# usb-isolator.net
KiCad netlist of a schematic drawn in EAGLE
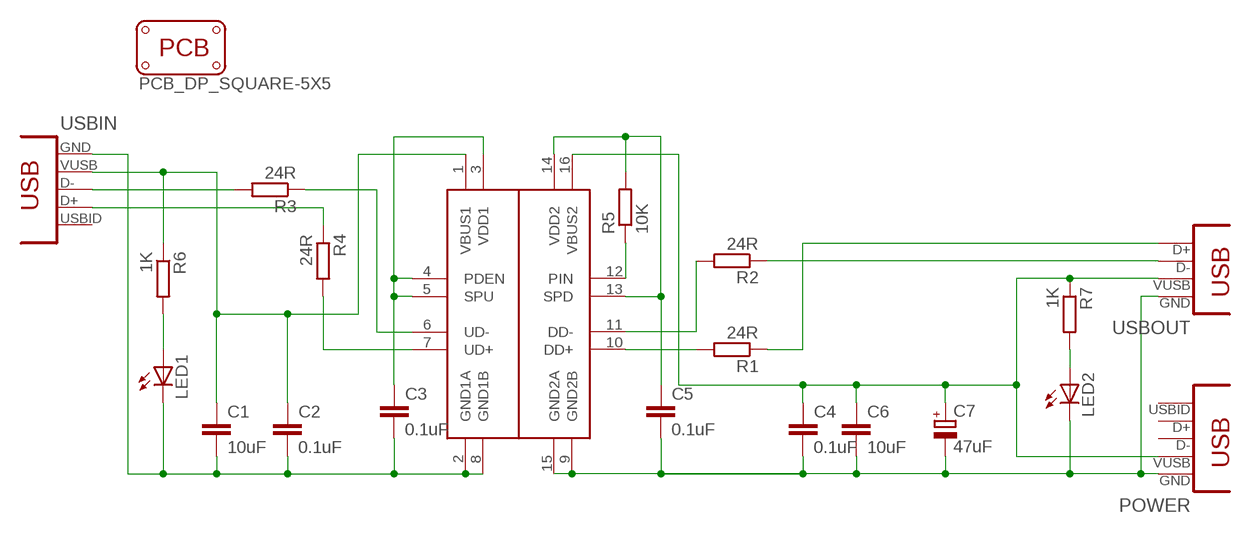
[diagram p0: schematic, sheet 1]

(export (version "E")
  (design (tool "Eeschema 10.0.6"))
  (components
    (comp (ref "C1")
      (value "10uF")
      (footprint "eagle-import:C0805K")
      (libsource (lib "eagle-import") (part "C-EUC0805K"))
    )
    (comp (ref "C2")
      (value "0.1uF")
      (footprint "eagle-import:C0805K")
      (libsource (lib "eagle-import") (part "C-EUC0805K"))
    )
    (comp (ref "C3")
      (value "0.1uF")
      (footprint "eagle-import:C0805K")
      (libsource (lib "eagle-import") (part "C-EUC0805K"))
    )
    (comp (ref "C4")
      (value "0.1uF")
      (footprint "eagle-import:C0805K")
      (libsource (lib "eagle-import") (part "C-EUC0805K"))
    )
    (comp (ref "C5")
      (value "0.1uF")
      (footprint "eagle-import:C0805K")
      (libsource (lib "eagle-import") (part "C-EUC0805K"))
    )
    (comp (ref "C6")
      (value "10uF")
      (footprint "eagle-import:C0805K")
      (libsource (lib "eagle-import") (part "C-EUC0805K"))
    )
    (comp (ref "C7")
      (value "47uF")
      (footprint "eagle-import:D_7343-31W")
      (libsource (lib "eagle-import") (part "CPOL-EUD/7343-31W"))
    )
    (comp (ref "IC1")
      (value "ADUM3160BRWZ")
      (footprint "eagle-import:SO16W")
      (libsource (lib "eagle-import") (part "ADUM3160BRWZ"))
    )
    (comp (ref "LED1")
      (value "LED-0805")
      (footprint "eagle-import:LED-805")
      (libsource (lib "eagle-import") (part "LED-0805"))
    )
    (comp (ref "LED2")
      (value "LED-0805")
      (footprint "eagle-import:LED-805")
      (libsource (lib "eagle-import") (part "LED-0805"))
    )
    (comp (ref "POWER")
      (value "CON-USB-F-MINI-B")
      (footprint "eagle-import:CONN_USB_MINI-B")
      (libsource (lib "eagle-import") (part "CON-USB-F-MINI-B"))
    )
    (comp (ref "R1")
      (value "24R")
      (footprint "eagle-import:M0805")
      (libsource (lib "eagle-import") (part "R-EU_M0805"))
    )
    (comp (ref "R2")
      (value "24R")
      (footprint "eagle-import:M0805")
      (libsource (lib "eagle-import") (part "R-EU_M0805"))
    )
    (comp (ref "R3")
      (value "24R")
      (footprint "eagle-import:M0805")
      (libsource (lib "eagle-import") (part "R-EU_M0805"))
    )
    (comp (ref "R4")
      (value "24R")
      (footprint "eagle-import:M0805")
      (libsource (lib "eagle-import") (part "R-EU_M0805"))
    )
    (comp (ref "R5")
      (value "10K")
      (footprint "eagle-import:M0805")
      (libsource (lib "eagle-import") (part "R-EU_M0805"))
    )
    (comp (ref "R6")
      (value "1K")
      (footprint "eagle-import:M0805")
      (libsource (lib "eagle-import") (part "R-EU_M0805"))
    )
    (comp (ref "R7")
      (value "1K")
      (footprint "eagle-import:M0805")
      (libsource (lib "eagle-import") (part "R-EU_M0805"))
    )
    (comp (ref "USB-ISOLATOR")
      (value "PCB_DP_SQUARE-5X5")
      (footprint "eagle-import:DP5050_V1")
      (libsource (lib "eagle-import") (part "PCB_DP_SQUARE-5X5"))
    )
    (comp (ref "USBIN")
      (value "CON-USB-F-MINI-B")
      (footprint "eagle-import:CONN_USB_MINI-B")
      (libsource (lib "eagle-import") (part "CON-USB-F-MINI-B"))
    )
    (comp (ref "USBOUT")
      (value "CON-USB-F-2PB")
      (footprint "eagle-import:CONN_USB_A_F")
      (libsource (lib "eagle-import") (part "CON-USB-F-2PB"))
    )
  )
  (nets
    (net (code "1") (name "Net-(IC1-DD+)") (class "Default")
      (node (ref "IC1") (pin "10") (pinfunction "DD+_10") (pintype "bidirectional"))
      (node (ref "R1") (pin "2") (pinfunction "2_2") (pintype "passive"))
    )
    (net (code "2") (name "Net-(IC1-DD-)") (class "Default")
      (node (ref "IC1") (pin "11") (pinfunction "DD-_11") (pintype "bidirectional"))
      (node (ref "R2") (pin "2") (pinfunction "2_2") (pintype "passive"))
    )
    (net (code "3") (name "Net-(IC1-GND1A)") (class "Default")
      (node (ref "C1") (pin "2") (pinfunction "2_2") (pintype "passive"))
      (node (ref "C2") (pin "2") (pinfunction "2_2") (pintype "passive"))
      (node (ref "C3") (pin "2") (pinfunction "2_2") (pintype "passive"))
      (node (ref "IC1") (pin "2") (pinfunction "GND1A_2") (pintype "power_in"))
      (node (ref "IC1") (pin "8") (pinfunction "GND1B_8") (pintype "power_in"))
      (node (ref "LED1") (pin "C") (pinfunction "C_C") (pintype "passive"))
      (node (ref "USBIN") (pin "GND") (pinfunction "GND_GND") (pintype "bidirectional"))
    )
    (net (code "4") (name "Net-(IC1-GND2A)") (class "Default")
      (node (ref "C4") (pin "2") (pinfunction "2_2") (pintype "passive"))
      (node (ref "C5") (pin "2") (pinfunction "2_2") (pintype "passive"))
      (node (ref "C6") (pin "2") (pinfunction "2_2") (pintype "passive"))
      (node (ref "C7") (pin "-") (pinfunction "-_-") (pintype "passive"))
      (node (ref "IC1") (pin "15") (pinfunction "GND2A_15") (pintype "power_in"))
      (node (ref "IC1") (pin "9") (pinfunction "GND2B_9") (pintype "power_in"))
      (node (ref "LED2") (pin "C") (pinfunction "C_C") (pintype "passive"))
      (node (ref "POWER") (pin "GND") (pinfunction "GND_GND") (pintype "bidirectional"))
      (node (ref "USBOUT") (pin "4") (pinfunction "GND_4") (pintype "bidirectional"))
    )
    (net (code "5") (name "Net-(IC1-PDEN)") (class "Default")
      (node (ref "C3") (pin "1") (pinfunction "1_1") (pintype "passive"))
      (node (ref "IC1") (pin "3") (pinfunction "VDD1_3") (pintype "power_in"))
      (node (ref "IC1") (pin "4") (pinfunction "PDEN_4") (pintype "input"))
      (node (ref "IC1") (pin "5") (pinfunction "SPU_5") (pintype "input"))
    )
    (net (code "6") (name "Net-(IC1-PIN)") (class "Default")
      (node (ref "IC1") (pin "12") (pinfunction "PIN_12") (pintype "input"))
      (node (ref "R5") (pin "1") (pinfunction "1_1") (pintype "passive"))
    )
    (net (code "7") (name "Net-(IC1-SPD)") (class "Default")
      (node (ref "C5") (pin "1") (pinfunction "1_1") (pintype "passive"))
      (node (ref "IC1") (pin "13") (pinfunction "SPD_13") (pintype "input"))
      (node (ref "IC1") (pin "14") (pinfunction "VDD2_14") (pintype "bidirectional"))
      (node (ref "R5") (pin "2") (pinfunction "2_2") (pintype "passive"))
    )
    (net (code "8") (name "Net-(IC1-UD+)") (class "Default")
      (node (ref "IC1") (pin "7") (pinfunction "UD+_7") (pintype "bidirectional"))
      (node (ref "R4") (pin "2") (pinfunction "2_2") (pintype "passive"))
    )
    (net (code "9") (name "Net-(IC1-UD-)") (class "Default")
      (node (ref "IC1") (pin "6") (pinfunction "UD-_6") (pintype "bidirectional"))
      (node (ref "R3") (pin "1") (pinfunction "1_1") (pintype "passive"))
    )
    (net (code "10") (name "Net-(IC1-VBUS1)") (class "Default")
      (node (ref "C1") (pin "1") (pinfunction "1_1") (pintype "passive"))
      (node (ref "C2") (pin "1") (pinfunction "1_1") (pintype "passive"))
      (node (ref "IC1") (pin "1") (pinfunction "VBUS1_1") (pintype "power_in"))
      (node (ref "R6") (pin "1") (pinfunction "1_1") (pintype "passive"))
      (node (ref "USBIN") (pin "VUSB") (pinfunction "VUSB_VUSB") (pintype "bidirectional"))
    )
    (net (code "11") (name "Net-(IC1-VBUS2)") (class "Default")
      (node (ref "C4") (pin "1") (pinfunction "1_1") (pintype "passive"))
      (node (ref "C6") (pin "1") (pinfunction "1_1") (pintype "passive"))
      (node (ref "C7") (pin "+") (pinfunction "+_+") (pintype "passive"))
      (node (ref "IC1") (pin "16") (pinfunction "VBUS2_16") (pintype "bidirectional"))
      (node (ref "POWER") (pin "VUSB") (pinfunction "VUSB_VUSB") (pintype "bidirectional"))
      (node (ref "R7") (pin "1") (pinfunction "1_1") (pintype "passive"))
      (node (ref "USBOUT") (pin "1") (pinfunction "VUSB_1") (pintype "bidirectional"))
    )
    (net (code "12") (name "Net-(LED1-PadA)") (class "Default")
      (node (ref "LED1") (pin "A") (pinfunction "A_A") (pintype "passive"))
      (node (ref "R6") (pin "2") (pinfunction "2_2") (pintype "passive"))
    )
    (net (code "13") (name "Net-(LED2-PadA)") (class "Default")
      (node (ref "LED2") (pin "A") (pinfunction "A_A") (pintype "passive"))
      (node (ref "R7") (pin "2") (pinfunction "2_2") (pintype "passive"))
    )
    (net (code "14") (name "Net-(R3-Pad2)") (class "Default")
      (node (ref "R3") (pin "2") (pinfunction "2_2") (pintype "passive"))
      (node (ref "USBIN") (pin "D-") (pinfunction "D-_D-") (pintype "bidirectional"))
    )
    (net (code "15") (name "Net-(R4-Pad1)") (class "Default")
      (node (ref "R4") (pin "1") (pinfunction "1_1") (pintype "passive"))
      (node (ref "USBIN") (pin "D+") (pinfunction "D+_D+") (pintype "bidirectional"))
    )
    (net (code "16") (name "Net-(USBOUTB-D+)") (class "Default")
      (node (ref "R1") (pin "1") (pinfunction "1_1") (pintype "passive"))
      (node (ref "USBOUT") (pin "3") (pinfunction "D+_3") (pintype "bidirectional"))
    )
    (net (code "17") (name "Net-(USBOUTB-D-)") (class "Default")
      (node (ref "R2") (pin "1") (pinfunction "1_1") (pintype "passive"))
      (node (ref "USBOUT") (pin "2") (pinfunction "D-_2") (pintype "bidirectional"))
    )
    (net (code "18") (name "unconnected-(POWER-PadD+)") (class "Default")
      (node (ref "POWER") (pin "D+") (pinfunction "D+_D+") (pintype "bidirectional"))
    )
    (net (code "19") (name "unconnected-(POWER-PadD-)") (class "Default")
      (node (ref "POWER") (pin "D-") (pinfunction "D-_D-") (pintype "bidirectional"))
    )
    (net (code "20") (name "unconnected-(POWERB-USBID-PadID)") (class "Default")
      (node (ref "POWER") (pin "ID") (pinfunction "USBID_ID") (pintype "bidirectional"))
    )
    (net (code "21") (name "unconnected-(USBINB-USBID-PadID)") (class "Default")
      (node (ref "USBIN") (pin "ID") (pinfunction "USBID_ID") (pintype "bidirectional"))
    )
  )
)
